# PCB.net
KiCad netlist of a schematic drawn in EasyEDA Pro
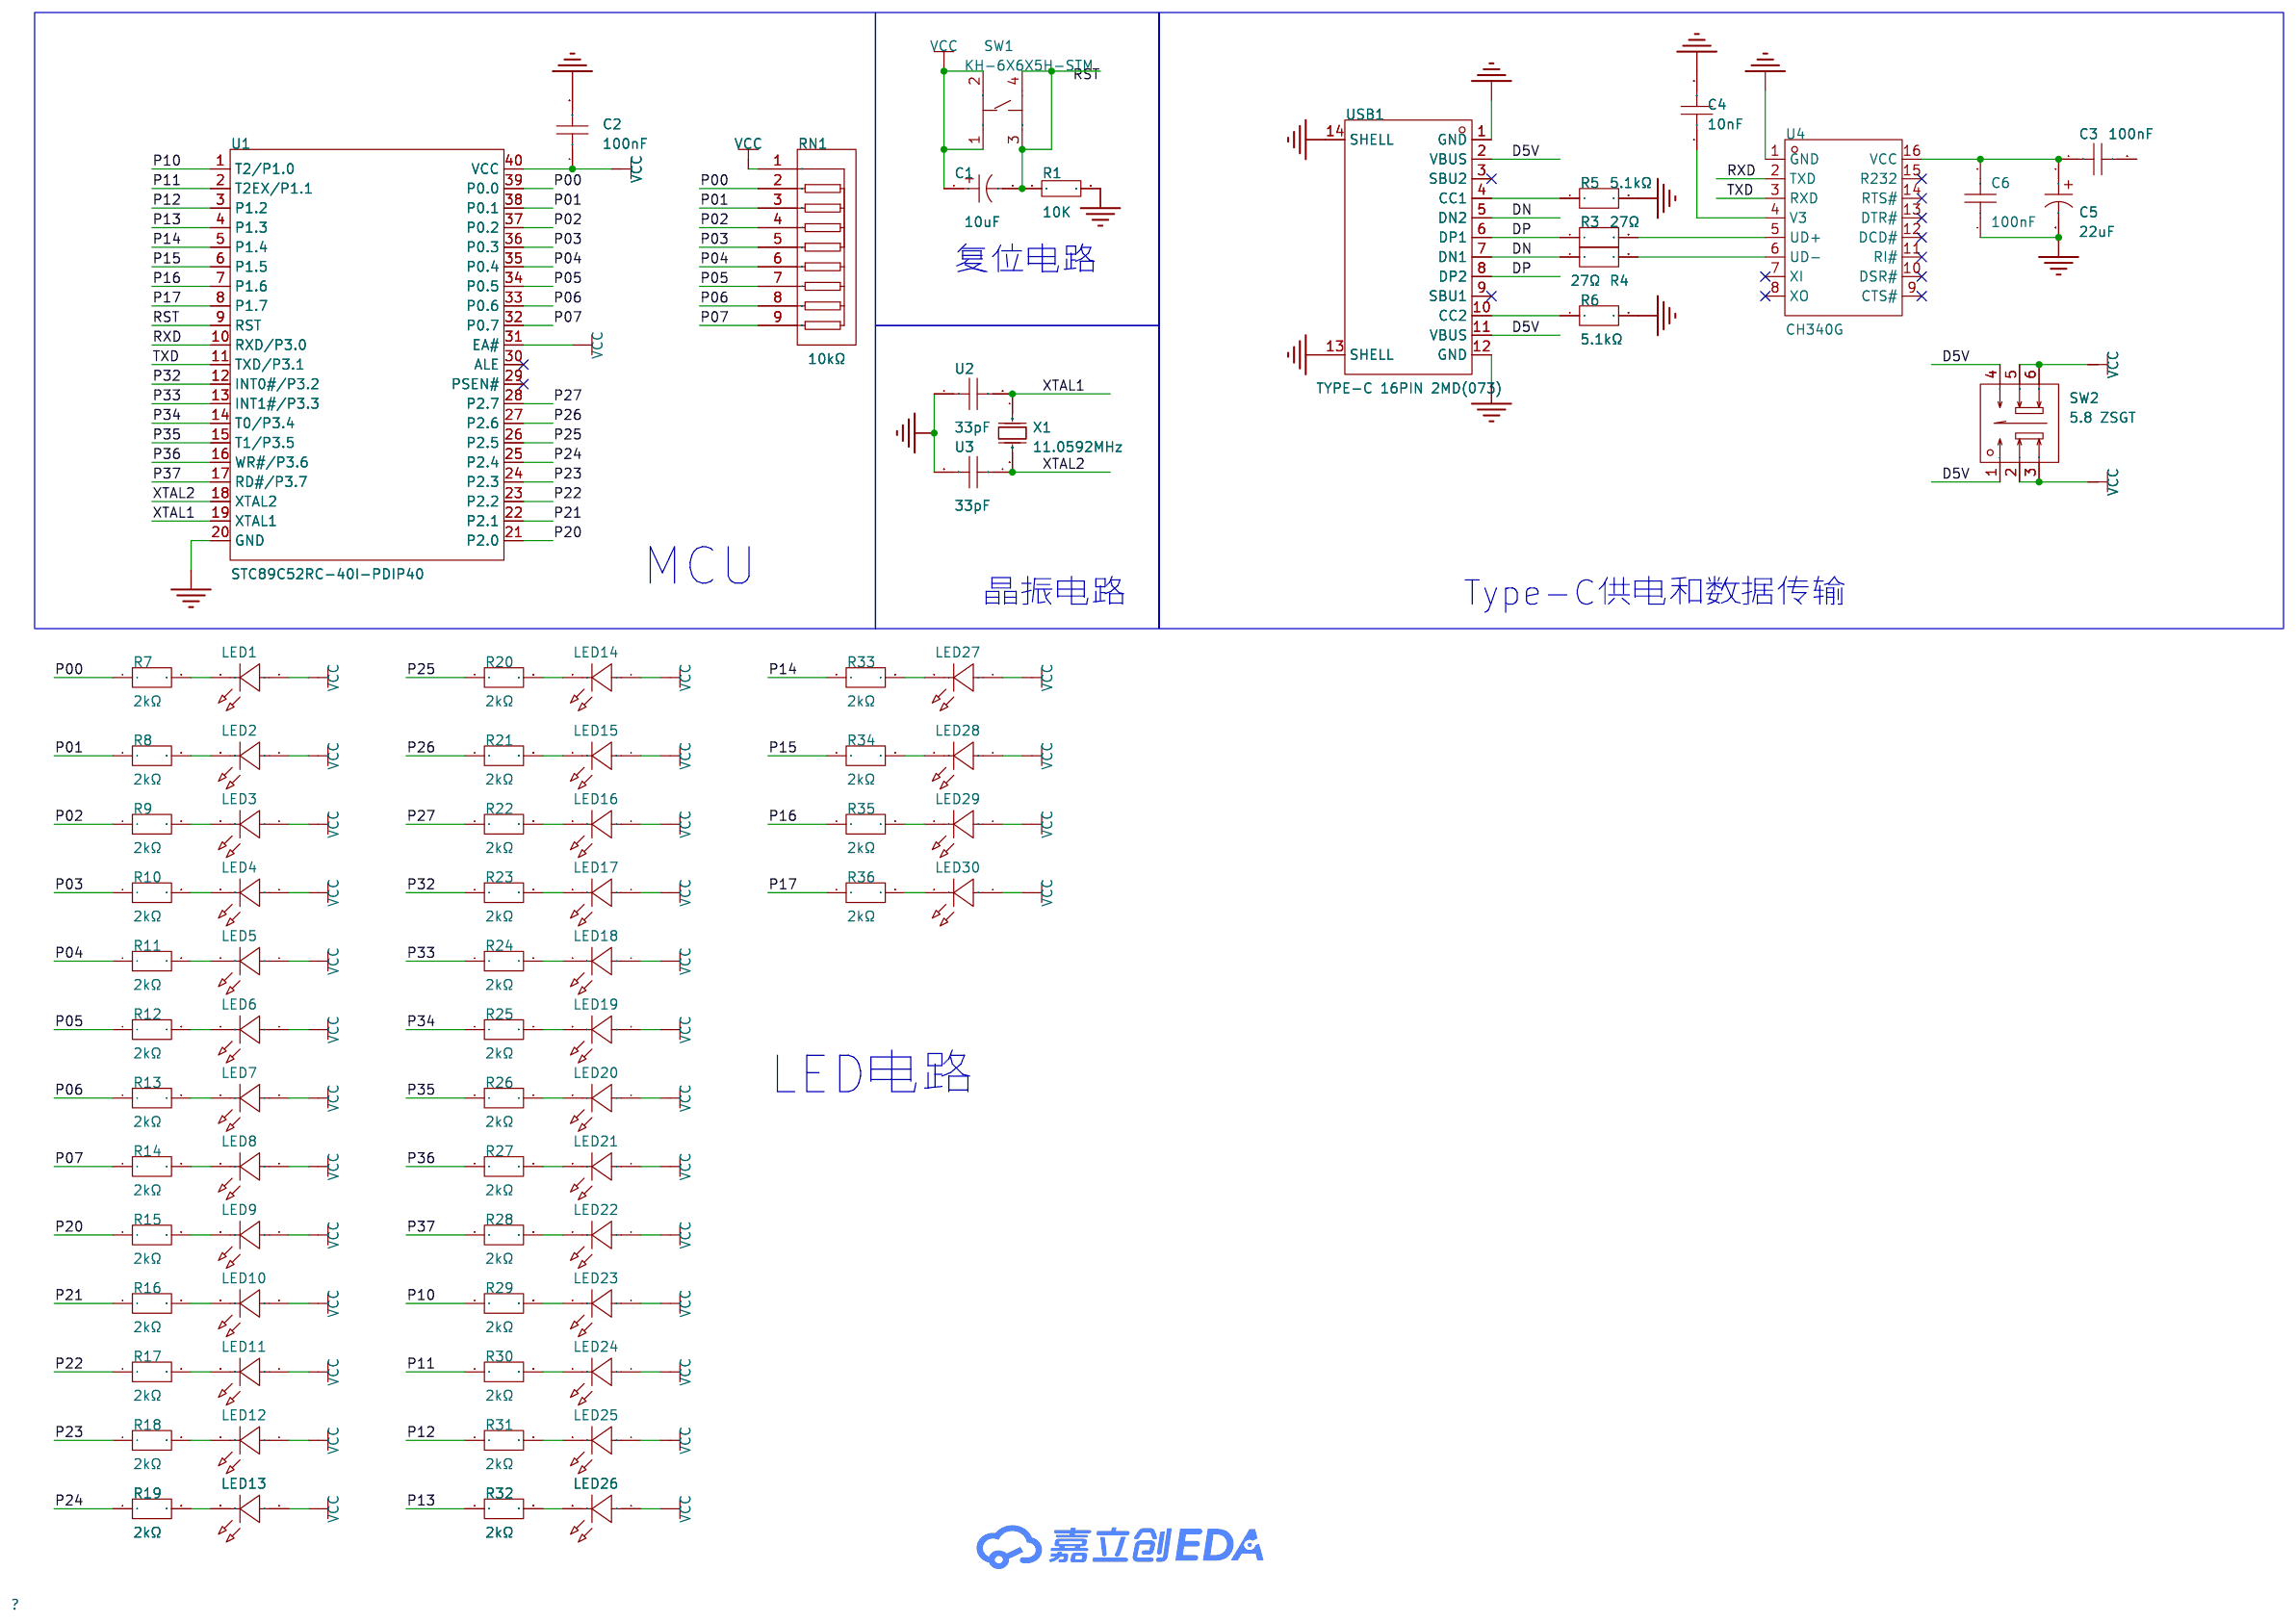
[diagram p0: schematic sheet]

(export (version "E")
  (design (tool "Eeschema 10.0.6"))
  (components
    (comp (ref "C1")
      (value "10uF")
      (footprint "easyedapro:CAP-TH_BD10.0-P5.00-D0.6-FD_1")
      (description "容值:10uF;精度:±20%;额定电压:450V;纹波电流:200mA@100kHz;等效串联电阻(ESR):9Ω@100kHz;")
      (fields (field (name "Manufacturer Part") "CV100MPA16B") (field (name "Manufacturer") "TWBOR(伯鸿)"))
      (libsource (lib "easyedapro") (part "CV100MPA16B"))
    )
    (comp (ref "C2")
      (value "100nF")
      (footprint "easyedapro:C0603")
      (description "容值:100nF;精度:±10%;额定电压:25V;温度系数:X7R;")
      (fields
        (field (name "Manufacturer Part") "0603X7R104K250NT")
        (field (name "Manufacturer") "AIDE(爱迪电容)")
      )
      (libsource (lib "easyedapro") (part "0603X7R104K250NT"))
    )
    (comp (ref "C3")
      (value "100nF")
      (footprint "easyedapro:C0603")
      (description "容值:100nF;精度:±10%;额定电压:25V;温度系数:X7R;")
      (fields
        (field (name "Manufacturer Part") "0603X7R104K250NT")
        (field (name "Manufacturer") "AIDE(爱迪电容)")
      )
      (libsource (lib "easyedapro") (part "0603X7R104K250NT"))
    )
    (comp (ref "C4")
      (value "10nF")
      (footprint "easyedapro:C0603")
      (description "容值:10nF;精度:±10%;额定电压:200V;温度系数:X7R;")
      (fields
        (field (name "Manufacturer Part") "C0603X103K2RECAUTO")
        (field (name "Manufacturer") "KEMET(基美)")
      )
      (libsource (lib "easyedapro") (part "C0603X103K2RECAUTO"))
    )
    (comp (ref "C5")
      (value "22uF")
      (footprint "easyedapro:CAP-SMD_BD5.0-L5.3-W5.3-LS6.0-FD-H5.7")
      (description "容值:22uF;精度:±20%;额定电压:35V;纹波电流:95mA@120Hz;等效串联电阻(ESR):1.8Ω;")
      (fields (field (name "Manufacturer Part") "JVE35V22M5X6") (field (name "Manufacturer") "捷而瑞"))
      (libsource (lib "easyedapro") (part "JVE35V22M5X6"))
    )
    (comp (ref "C6")
      (value "100nF")
      (footprint "easyedapro:C0603")
      (description "容值:100nF;精度:±10%;额定电压:25V;温度系数:X7R;")
      (fields
        (field (name "Manufacturer Part") "0603X7R104K250NT")
        (field (name "Manufacturer") "AIDE(爱迪电容)")
      )
      (libsource (lib "easyedapro") (part "0603X7R104K250NT"))
    )
    (comp (ref "LED1")
      (value "L-7113SGC")
      (footprint "easyedapro:LED-TH_BD5.9-P2.54-FD")
      (fields (field (name "Manufacturer") "Kingbright"))
      (libsource (lib "easyedapro") (part "L-7113SGC"))
    )
    (comp (ref "LED2")
      (value "L-7113SGC")
      (footprint "easyedapro:LED-TH_BD5.9-P2.54-FD")
      (fields (field (name "Manufacturer") "Kingbright"))
      (libsource (lib "easyedapro") (part "L-7113SGC"))
    )
    (comp (ref "LED3")
      (value "L-7113SGC")
      (footprint "easyedapro:LED-TH_BD5.9-P2.54-FD")
      (fields (field (name "Manufacturer") "Kingbright"))
      (libsource (lib "easyedapro") (part "L-7113SGC"))
    )
    (comp (ref "LED4")
      (value "L-7113SGC")
      (footprint "easyedapro:LED-TH_BD5.9-P2.54-FD")
      (fields (field (name "Manufacturer") "Kingbright"))
      (libsource (lib "easyedapro") (part "L-7113SGC"))
    )
    (comp (ref "LED5")
      (value "L-7113SGC")
      (footprint "easyedapro:LED-TH_BD5.9-P2.54-FD")
      (fields (field (name "Manufacturer") "Kingbright"))
      (libsource (lib "easyedapro") (part "L-7113SGC"))
    )
    (comp (ref "LED6")
      (value "L-7113SGC")
      (footprint "easyedapro:LED-TH_BD5.9-P2.54-FD")
      (fields (field (name "Manufacturer") "Kingbright"))
      (libsource (lib "easyedapro") (part "L-7113SGC"))
    )
    (comp (ref "LED7")
      (value "L-7113SGC")
      (footprint "easyedapro:LED-TH_BD5.9-P2.54-FD")
      (fields (field (name "Manufacturer") "Kingbright"))
      (libsource (lib "easyedapro") (part "L-7113SGC"))
    )
    (comp (ref "LED8")
      (value "L-7113SGC")
      (footprint "easyedapro:LED-TH_BD5.9-P2.54-FD")
      (fields (field (name "Manufacturer") "Kingbright"))
      (libsource (lib "easyedapro") (part "L-7113SGC"))
    )
    (comp (ref "LED9")
      (value "L-7113SGC")
      (footprint "easyedapro:LED-TH_BD5.9-P2.54-FD")
      (fields (field (name "Manufacturer") "Kingbright"))
      (libsource (lib "easyedapro") (part "L-7113SGC"))
    )
    (comp (ref "LED10")
      (value "L-7113SGC")
      (footprint "easyedapro:LED-TH_BD5.9-P2.54-FD")
      (fields (field (name "Manufacturer") "Kingbright"))
      (libsource (lib "easyedapro") (part "L-7113SGC"))
    )
    (comp (ref "LED11")
      (value "L-7113SGC")
      (footprint "easyedapro:LED-TH_BD5.9-P2.54-FD")
      (fields (field (name "Manufacturer") "Kingbright"))
      (libsource (lib "easyedapro") (part "L-7113SGC"))
    )
    (comp (ref "LED12")
      (value "L-7113SGC")
      (footprint "easyedapro:LED-TH_BD5.9-P2.54-FD")
      (fields (field (name "Manufacturer") "Kingbright"))
      (libsource (lib "easyedapro") (part "L-7113SGC"))
    )
    (comp (ref "LED13")
      (value "L-7113SGC")
      (footprint "easyedapro:LED-TH_BD5.9-P2.54-FD")
      (fields (field (name "Manufacturer") "Kingbright"))
      (libsource (lib "easyedapro") (part "L-7113SGC"))
    )
    (comp (ref "LED14")
      (value "L-7113SGC")
      (footprint "easyedapro:LED-TH_BD5.9-P2.54-FD")
      (fields (field (name "Manufacturer") "Kingbright"))
      (libsource (lib "easyedapro") (part "L-7113SGC"))
    )
    (comp (ref "LED15")
      (value "L-7113SGC")
      (footprint "easyedapro:LED-TH_BD5.9-P2.54-FD")
      (fields (field (name "Manufacturer") "Kingbright"))
      (libsource (lib "easyedapro") (part "L-7113SGC"))
    )
    (comp (ref "LED16")
      (value "L-7113SGC")
      (footprint "easyedapro:LED-TH_BD5.9-P2.54-FD")
      (fields (field (name "Manufacturer") "Kingbright"))
      (libsource (lib "easyedapro") (part "L-7113SGC"))
    )
    (comp (ref "LED17")
      (value "L-7113SGC")
      (footprint "easyedapro:LED-TH_BD5.9-P2.54-FD")
      (fields (field (name "Manufacturer") "Kingbright"))
      (libsource (lib "easyedapro") (part "L-7113SGC"))
    )
    (comp (ref "LED18")
      (value "L-7113SGC")
      (footprint "easyedapro:LED-TH_BD5.9-P2.54-FD")
      (fields (field (name "Manufacturer") "Kingbright"))
      (libsource (lib "easyedapro") (part "L-7113SGC"))
    )
    (comp (ref "LED19")
      (value "L-7113SGC")
      (footprint "easyedapro:LED-TH_BD5.9-P2.54-FD")
      (fields (field (name "Manufacturer") "Kingbright"))
      (libsource (lib "easyedapro") (part "L-7113SGC"))
    )
    (comp (ref "LED20")
      (value "L-7113SGC")
      (footprint "easyedapro:LED-TH_BD5.9-P2.54-FD")
      (fields (field (name "Manufacturer") "Kingbright"))
      (libsource (lib "easyedapro") (part "L-7113SGC"))
    )
    (comp (ref "LED21")
      (value "L-7113SGC")
      (footprint "easyedapro:LED-TH_BD5.9-P2.54-FD")
      (fields (field (name "Manufacturer") "Kingbright"))
      (libsource (lib "easyedapro") (part "L-7113SGC"))
    )
    (comp (ref "LED22")
      (value "L-7113SGC")
      (footprint "easyedapro:LED-TH_BD5.9-P2.54-FD")
      (fields (field (name "Manufacturer") "Kingbright"))
      (libsource (lib "easyedapro") (part "L-7113SGC"))
    )
    (comp (ref "LED23")
      (value "L-7113SGC")
      (footprint "easyedapro:LED-TH_BD5.9-P2.54-FD")
      (fields (field (name "Manufacturer") "Kingbright"))
      (libsource (lib "easyedapro") (part "L-7113SGC"))
    )
    (comp (ref "LED24")
      (value "L-7113SGC")
      (footprint "easyedapro:LED-TH_BD5.9-P2.54-FD")
      (fields (field (name "Manufacturer") "Kingbright"))
      (libsource (lib "easyedapro") (part "L-7113SGC"))
    )
    (comp (ref "LED25")
      (value "L-7113SGC")
      (footprint "easyedapro:LED-TH_BD5.9-P2.54-FD")
      (fields (field (name "Manufacturer") "Kingbright"))
      (libsource (lib "easyedapro") (part "L-7113SGC"))
    )
    (comp (ref "LED26")
      (value "L-7113SGC")
      (footprint "easyedapro:LED-TH_BD5.9-P2.54-FD")
      (fields (field (name "Manufacturer") "Kingbright"))
      (libsource (lib "easyedapro") (part "L-7113SGC"))
    )
    (comp (ref "LED27")
      (value "L-7113SGC")
      (footprint "easyedapro:LED-TH_BD5.9-P2.54-FD")
      (fields (field (name "Manufacturer") "Kingbright"))
      (libsource (lib "easyedapro") (part "L-7113SGC"))
    )
    (comp (ref "LED28")
      (value "L-7113SGC")
      (footprint "easyedapro:LED-TH_BD5.9-P2.54-FD")
      (fields (field (name "Manufacturer") "Kingbright"))
      (libsource (lib "easyedapro") (part "L-7113SGC"))
    )
    (comp (ref "LED29")
      (value "L-7113SGC")
      (footprint "easyedapro:LED-TH_BD5.9-P2.54-FD")
      (fields (field (name "Manufacturer") "Kingbright"))
      (libsource (lib "easyedapro") (part "L-7113SGC"))
    )
    (comp (ref "LED30")
      (value "L-7113SGC")
      (footprint "easyedapro:LED-TH_BD5.9-P2.54-FD")
      (fields (field (name "Manufacturer") "Kingbright"))
      (libsource (lib "easyedapro") (part "L-7113SGC"))
    )
    (comp (ref "R1") (value "10K") (footprint "easyedapro:R0603") (libsource (lib "easyedapro") (part "电阻")))
    (comp (ref "R3")
      (value "27Ω")
      (footprint "easyedapro:R0805")
      (description "电阻类型:厚膜电阻;阻值:27Ω;精度:±5%;功率:125mW;工作电压:150V;温度系数:±100ppm/°C;")
      (fields (field (name "Manufacturer Part") "FRC0805J270 TS") (field (name "Manufacturer") "FOJAN(富捷)"))
      (libsource (lib "easyedapro") (part "FRC0805J270 TS"))
    )
    (comp (ref "R4")
      (value "27Ω")
      (footprint "easyedapro:R0805")
      (description "电阻类型:厚膜电阻;阻值:27Ω;精度:±5%;功率:125mW;工作电压:150V;温度系数:±100ppm/°C;")
      (fields (field (name "Manufacturer Part") "FRC0805J270 TS") (field (name "Manufacturer") "FOJAN(富捷)"))
      (libsource (lib "easyedapro") (part "FRC0805J270 TS"))
    )
    (comp (ref "R5")
      (value "5.1kΩ")
      (footprint "easyedapro:R0603")
      (description "电阻类型:薄膜电阻;阻值:5.1kΩ;精度:±0.01%;功率:100mW;温度系数:±2ppm/°C;")
      (fields
        (field (name "Manufacturer Part") "RNCF0603TKW5K10")
        (field (name "Manufacturer") "SEI(Stackpole Electronics Inc.)")
      )
      (libsource (lib "easyedapro") (part "RNCF0603TKW5K10"))
    )
    (comp (ref "R6")
      (value "5.1kΩ")
      (footprint "easyedapro:R0603")
      (description "电阻类型:薄膜电阻;阻值:5.1kΩ;精度:±0.01%;功率:100mW;温度系数:±2ppm/°C;")
      (fields
        (field (name "Manufacturer Part") "RNCF0603TKW5K10")
        (field (name "Manufacturer") "SEI(Stackpole Electronics Inc.)")
      )
      (libsource (lib "easyedapro") (part "RNCF0603TKW5K10"))
    )
    (comp (ref "R7")
      (value "2kΩ")
      (footprint "easyedapro:R0402")
      (description "电阻类型:厚膜电阻;阻值:2kΩ;精度:±1%;功率:200mW;工作电压:50V;温度系数:±100ppm/°C;")
      (fields (field (name "Manufacturer Part") "RCS04022K00FKED") (field (name "Manufacturer") "VISHAY(威世)"))
      (libsource (lib "easyedapro") (part "RCS04022K00FKED"))
    )
    (comp (ref "R8")
      (value "2kΩ")
      (footprint "easyedapro:R0402")
      (description "电阻类型:厚膜电阻;阻值:2kΩ;精度:±1%;功率:200mW;工作电压:50V;温度系数:±100ppm/°C;")
      (fields (field (name "Manufacturer Part") "RCS04022K00FKED") (field (name "Manufacturer") "VISHAY(威世)"))
      (libsource (lib "easyedapro") (part "RCS04022K00FKED"))
    )
    (comp (ref "R9")
      (value "2kΩ")
      (footprint "easyedapro:R0402")
      (description "电阻类型:厚膜电阻;阻值:2kΩ;精度:±1%;功率:200mW;工作电压:50V;温度系数:±100ppm/°C;")
      (fields (field (name "Manufacturer Part") "RCS04022K00FKED") (field (name "Manufacturer") "VISHAY(威世)"))
      (libsource (lib "easyedapro") (part "RCS04022K00FKED"))
    )
    (comp (ref "R10")
      (value "2kΩ")
      (footprint "easyedapro:R0402")
      (description "电阻类型:厚膜电阻;阻值:2kΩ;精度:±1%;功率:200mW;工作电压:50V;温度系数:±100ppm/°C;")
      (fields (field (name "Manufacturer Part") "RCS04022K00FKED") (field (name "Manufacturer") "VISHAY(威世)"))
      (libsource (lib "easyedapro") (part "RCS04022K00FKED"))
    )
    (comp (ref "R11")
      (value "2kΩ")
      (footprint "easyedapro:R0402")
      (description "电阻类型:厚膜电阻;阻值:2kΩ;精度:±1%;功率:200mW;工作电压:50V;温度系数:±100ppm/°C;")
      (fields (field (name "Manufacturer Part") "RCS04022K00FKED") (field (name "Manufacturer") "VISHAY(威世)"))
      (libsource (lib "easyedapro") (part "RCS04022K00FKED"))
    )
    (comp (ref "R12")
      (value "2kΩ")
      (footprint "easyedapro:R0402")
      (description "电阻类型:厚膜电阻;阻值:2kΩ;精度:±1%;功率:200mW;工作电压:50V;温度系数:±100ppm/°C;")
      (fields (field (name "Manufacturer Part") "RCS04022K00FKED") (field (name "Manufacturer") "VISHAY(威世)"))
      (libsource (lib "easyedapro") (part "RCS04022K00FKED"))
    )
    (comp (ref "R13")
      (value "2kΩ")
      (footprint "easyedapro:R0402")
      (description "电阻类型:厚膜电阻;阻值:2kΩ;精度:±1%;功率:200mW;工作电压:50V;温度系数:±100ppm/°C;")
      (fields (field (name "Manufacturer Part") "RCS04022K00FKED") (field (name "Manufacturer") "VISHAY(威世)"))
      (libsource (lib "easyedapro") (part "RCS04022K00FKED"))
    )
    (comp (ref "R14")
      (value "2kΩ")
      (footprint "easyedapro:R0402")
      (description "电阻类型:厚膜电阻;阻值:2kΩ;精度:±1%;功率:200mW;工作电压:50V;温度系数:±100ppm/°C;")
      (fields (field (name "Manufacturer Part") "RCS04022K00FKED") (field (name "Manufacturer") "VISHAY(威世)"))
      (libsource (lib "easyedapro") (part "RCS04022K00FKED"))
    )
    (comp (ref "R15")
      (value "2kΩ")
      (footprint "easyedapro:R0402")
      (description "电阻类型:厚膜电阻;阻值:2kΩ;精度:±1%;功率:200mW;工作电压:50V;温度系数:±100ppm/°C;")
      (fields (field (name "Manufacturer Part") "RCS04022K00FKED") (field (name "Manufacturer") "VISHAY(威世)"))
      (libsource (lib "easyedapro") (part "RCS04022K00FKED"))
    )
    (comp (ref "R16")
      (value "2kΩ")
      (footprint "easyedapro:R0402")
      (description "电阻类型:厚膜电阻;阻值:2kΩ;精度:±1%;功率:200mW;工作电压:50V;温度系数:±100ppm/°C;")
      (fields (field (name "Manufacturer Part") "RCS04022K00FKED") (field (name "Manufacturer") "VISHAY(威世)"))
      (libsource (lib "easyedapro") (part "RCS04022K00FKED"))
    )
    (comp (ref "R17")
      (value "2kΩ")
      (footprint "easyedapro:R0402")
      (description "电阻类型:厚膜电阻;阻值:2kΩ;精度:±1%;功率:200mW;工作电压:50V;温度系数:±100ppm/°C;")
      (fields (field (name "Manufacturer Part") "RCS04022K00FKED") (field (name "Manufacturer") "VISHAY(威世)"))
      (libsource (lib "easyedapro") (part "RCS04022K00FKED"))
    )
    (comp (ref "R18")
      (value "2kΩ")
      (footprint "easyedapro:R0402")
      (description "电阻类型:厚膜电阻;阻值:2kΩ;精度:±1%;功率:200mW;工作电压:50V;温度系数:±100ppm/°C;")
      (fields (field (name "Manufacturer Part") "RCS04022K00FKED") (field (name "Manufacturer") "VISHAY(威世)"))
      (libsource (lib "easyedapro") (part "RCS04022K00FKED"))
    )
    (comp (ref "R19")
      (value "2kΩ")
      (footprint "easyedapro:R0402")
      (description "电阻类型:厚膜电阻;阻值:2kΩ;精度:±1%;功率:200mW;工作电压:50V;温度系数:±100ppm/°C;")
      (fields (field (name "Manufacturer Part") "RCS04022K00FKED") (field (name "Manufacturer") "VISHAY(威世)"))
      (libsource (lib "easyedapro") (part "RCS04022K00FKED"))
    )
    (comp (ref "R20")
      (value "2kΩ")
      (footprint "easyedapro:R0402")
      (description "电阻类型:厚膜电阻;阻值:2kΩ;精度:±1%;功率:200mW;工作电压:50V;温度系数:±100ppm/°C;")
      (fields (field (name "Manufacturer Part") "RCS04022K00FKED") (field (name "Manufacturer") "VISHAY(威世)"))
      (libsource (lib "easyedapro") (part "RCS04022K00FKED"))
    )
    (comp (ref "R21")
      (value "2kΩ")
      (footprint "easyedapro:R0402")
      (description "电阻类型:厚膜电阻;阻值:2kΩ;精度:±1%;功率:200mW;工作电压:50V;温度系数:±100ppm/°C;")
      (fields (field (name "Manufacturer Part") "RCS04022K00FKED") (field (name "Manufacturer") "VISHAY(威世)"))
      (libsource (lib "easyedapro") (part "RCS04022K00FKED"))
    )
    (comp (ref "R22")
      (value "2kΩ")
      (footprint "easyedapro:R0402")
      (description "电阻类型:厚膜电阻;阻值:2kΩ;精度:±1%;功率:200mW;工作电压:50V;温度系数:±100ppm/°C;")
      (fields (field (name "Manufacturer Part") "RCS04022K00FKED") (field (name "Manufacturer") "VISHAY(威世)"))
      (libsource (lib "easyedapro") (part "RCS04022K00FKED"))
    )
    (comp (ref "R23")
      (value "2kΩ")
      (footprint "easyedapro:R0402")
      (description "电阻类型:厚膜电阻;阻值:2kΩ;精度:±1%;功率:200mW;工作电压:50V;温度系数:±100ppm/°C;")
      (fields (field (name "Manufacturer Part") "RCS04022K00FKED") (field (name "Manufacturer") "VISHAY(威世)"))
      (libsource (lib "easyedapro") (part "RCS04022K00FKED"))
    )
    (comp (ref "R24")
      (value "2kΩ")
      (footprint "easyedapro:R0402")
      (description "电阻类型:厚膜电阻;阻值:2kΩ;精度:±1%;功率:200mW;工作电压:50V;温度系数:±100ppm/°C;")
      (fields (field (name "Manufacturer Part") "RCS04022K00FKED") (field (name "Manufacturer") "VISHAY(威世)"))
      (libsource (lib "easyedapro") (part "RCS04022K00FKED"))
    )
    (comp (ref "R25")
      (value "2kΩ")
      (footprint "easyedapro:R0402")
      (description "电阻类型:厚膜电阻;阻值:2kΩ;精度:±1%;功率:200mW;工作电压:50V;温度系数:±100ppm/°C;")
      (fields (field (name "Manufacturer Part") "RCS04022K00FKED") (field (name "Manufacturer") "VISHAY(威世)"))
      (libsource (lib "easyedapro") (part "RCS04022K00FKED"))
    )
    (comp (ref "R26")
      (value "2kΩ")
      (footprint "easyedapro:R0402")
      (description "电阻类型:厚膜电阻;阻值:2kΩ;精度:±1%;功率:200mW;工作电压:50V;温度系数:±100ppm/°C;")
      (fields (field (name "Manufacturer Part") "RCS04022K00FKED") (field (name "Manufacturer") "VISHAY(威世)"))
      (libsource (lib "easyedapro") (part "RCS04022K00FKED"))
    )
    (comp (ref "R27")
      (value "2kΩ")
      (footprint "easyedapro:R0402")
      (description "电阻类型:厚膜电阻;阻值:2kΩ;精度:±1%;功率:200mW;工作电压:50V;温度系数:±100ppm/°C;")
      (fields (field (name "Manufacturer Part") "RCS04022K00FKED") (field (name "Manufacturer") "VISHAY(威世)"))
      (libsource (lib "easyedapro") (part "RCS04022K00FKED"))
    )
    (comp (ref "R28")
      (value "2kΩ")
      (footprint "easyedapro:R0402")
      (description "电阻类型:厚膜电阻;阻值:2kΩ;精度:±1%;功率:200mW;工作电压:50V;温度系数:±100ppm/°C;")
      (fields (field (name "Manufacturer Part") "RCS04022K00FKED") (field (name "Manufacturer") "VISHAY(威世)"))
      (libsource (lib "easyedapro") (part "RCS04022K00FKED"))
    )
    (comp (ref "R29")
      (value "2kΩ")
      (footprint "easyedapro:R0402")
      (description "电阻类型:厚膜电阻;阻值:2kΩ;精度:±1%;功率:200mW;工作电压:50V;温度系数:±100ppm/°C;")
      (fields (field (name "Manufacturer Part") "RCS04022K00FKED") (field (name "Manufacturer") "VISHAY(威世)"))
      (libsource (lib "easyedapro") (part "RCS04022K00FKED"))
    )
    (comp (ref "R30")
      (value "2kΩ")
      (footprint "easyedapro:R0402")
      (description "电阻类型:厚膜电阻;阻值:2kΩ;精度:±1%;功率:200mW;工作电压:50V;温度系数:±100ppm/°C;")
      (fields (field (name "Manufacturer Part") "RCS04022K00FKED") (field (name "Manufacturer") "VISHAY(威世)"))
      (libsource (lib "easyedapro") (part "RCS04022K00FKED"))
    )
    (comp (ref "R31")
      (value "2kΩ")
      (footprint "easyedapro:R0402")
      (description "电阻类型:厚膜电阻;阻值:2kΩ;精度:±1%;功率:200mW;工作电压:50V;温度系数:±100ppm/°C;")
      (fields (field (name "Manufacturer Part") "RCS04022K00FKED") (field (name "Manufacturer") "VISHAY(威世)"))
      (libsource (lib "easyedapro") (part "RCS04022K00FKED"))
    )
    (comp (ref "R32")
      (value "2kΩ")
      (footprint "easyedapro:R0402")
      (description "电阻类型:厚膜电阻;阻值:2kΩ;精度:±1%;功率:200mW;工作电压:50V;温度系数:±100ppm/°C;")
      (fields (field (name "Manufacturer Part") "RCS04022K00FKED") (field (name "Manufacturer") "VISHAY(威世)"))
      (libsource (lib "easyedapro") (part "RCS04022K00FKED"))
    )
    (comp (ref "R33")
      (value "2kΩ")
      (footprint "easyedapro:R0402")
      (description "电阻类型:厚膜电阻;阻值:2kΩ;精度:±1%;功率:200mW;工作电压:50V;温度系数:±100ppm/°C;")
      (fields (field (name "Manufacturer Part") "RCS04022K00FKED") (field (name "Manufacturer") "VISHAY(威世)"))
      (libsource (lib "easyedapro") (part "RCS04022K00FKED"))
    )
    (comp (ref "R34")
      (value "2kΩ")
      (footprint "easyedapro:R0402")
      (description "电阻类型:厚膜电阻;阻值:2kΩ;精度:±1%;功率:200mW;工作电压:50V;温度系数:±100ppm/°C;")
      (fields (field (name "Manufacturer Part") "RCS04022K00FKED") (field (name "Manufacturer") "VISHAY(威世)"))
      (libsource (lib "easyedapro") (part "RCS04022K00FKED"))
    )
    (comp (ref "R35")
      (value "2kΩ")
      (footprint "easyedapro:R0402")
      (description "电阻类型:厚膜电阻;阻值:2kΩ;精度:±1%;功率:200mW;工作电压:50V;温度系数:±100ppm/°C;")
      (fields (field (name "Manufacturer Part") "RCS04022K00FKED") (field (name "Manufacturer") "VISHAY(威世)"))
      (libsource (lib "easyedapro") (part "RCS04022K00FKED"))
    )
    (comp (ref "R36")
      (value "2kΩ")
      (footprint "easyedapro:R0402")
      (description "电阻类型:厚膜电阻;阻值:2kΩ;精度:±1%;功率:200mW;工作电压:50V;温度系数:±100ppm/°C;")
      (fields (field (name "Manufacturer Part") "RCS04022K00FKED") (field (name "Manufacturer") "VISHAY(威世)"))
      (libsource (lib "easyedapro") (part "RCS04022K00FKED"))
    )
    (comp (ref "RN1")
      (value "10kΩ")
      (footprint "easyedapro:RES-ARRAY-TH_9P-P2.54-D1.0")
      (description "电阻器数:-;阻值:-;单个元件功率:-;")
      (fields (field (name "Manufacturer Part") "排阻 10 K 5%"))
      (libsource (lib "easyedapro") (part "10 K 5%"))
    )
    (comp (ref "SW1")
      (value "KH-6X6X5H-STM")
      (footprint "easyedapro:SW-SMD_4P-L6.0-W6.0-P4.50-LS9.0_H5.0")
      (description "电路结构:单刀单掷;按钮形状:圆形按钮;安装方式:立贴;开关长度:6mm;开关宽度:6mm;开关高度:5mm;带支架:不带;触点电流:50mA;额定电压(DC):12V;机械寿命:8万次;")
      (fields (field (name "Manufacturer") "kinghelm(金航标)"))
      (libsource (lib "easyedapro") (part "KH-6X6X5H-STM"))
    )
    (comp (ref "SW2")
      (value "5.8 ZSGT")
      (footprint "easyedapro:SW-TH_5.8ZSGT")
      (description "电路结构:双刀双掷;自锁/无锁:自锁;安装方式:直插;触点电流:110mA;额定电压 (DC):30V;带灯:不带;作用力:1.5N;机械寿命:10万次;")
      (fields (field (name "Manufacturer") "SHOU HAN(首韩)"))
      (libsource (lib "easyedapro") (part "5.8 ZSGT"))
    )
    (comp (ref "U1")
      (value "STC89C52RC-40I-PDIP40")
      (footprint "easyedapro:DIP-40_L52.0-W13.7-P2.54-LS15.2-BL")
      (description "CPU内核:51系列;应用领域:-;")
      (fields (field (name "Manufacturer") "STC"))
      (libsource (lib "easyedapro") (part "STC89C52RC-40I"))
    )
    (comp (ref "U2")
      (value "33pF")
      (footprint "easyedapro:C0603")
      (description "容值:33pF;精度:±1%;额定电压:50V;温度系数:-;")
      (fields
        (field (name "Manufacturer Part") "GRM1885C1H330FA01D")
        (field (name "Manufacturer") "muRata(村田)")
      )
      (libsource (lib "easyedapro") (part "GRM1885C1H330FA01D"))
    )
    (comp (ref "U3")
      (value "33pF")
      (footprint "easyedapro:C0603")
      (description "容值:33pF;精度:±1%;额定电压:50V;温度系数:-;")
      (fields
        (field (name "Manufacturer Part") "GRM1885C1H330FA01D")
        (field (name "Manufacturer") "muRata(村田)")
      )
      (libsource (lib "easyedapro") (part "GRM1885C1H330FA01D"))
    )
    (comp (ref "U4")
      (value "CH340G")
      (footprint "easyedapro:SOIC-16_L9.9-W3.9-P1.27-LS6.0-BL")
      (description "应用功能:USB转UART;接口协议:USB 2.0;数据速率:2Mbps;")
      (fields (field (name "Manufacturer") "WCH(南京沁恒)"))
      (libsource (lib "easyedapro") (part "CH340G"))
    )
    (comp (ref "USB1")
      (value "TYPE-C 16PIN 2MD(073)")
      (footprint "easyedapro:USB-C-SMD_TYPE-C-6PIN-2MD-073")
      (description "连接器类型:Type-C;协议标准:USB 3.1;公母:母;安装方式:卧贴;触点数量:16P;端口数量:1;额定电流 - 电源:3A;工作温度:-25°C~+85°C;")
      (fields (field (name "Manufacturer") "SHOU HAN(首韩)"))
      (libsource (lib "easyedapro") (part "TYPE-C 16PIN 2MD(073)"))
    )
    (comp (ref "X1")
      (value "11.0592MHz")
      (footprint "easyedapro:HC-49US_L11.5-W4.5-P4.88")
      (description "晶振类型:直插晶振;频率:11.0592MHz;常温频差:±20ppm;负载电容:20pF;频率稳定度:±30ppm;")
      (fields
        (field (name "Manufacturer Part") "X49SD110592MSD2SC")
        (field (name "Manufacturer") "YXC(扬兴晶振)")
      )
      (libsource (lib "easyedapro") (part "X49SD110592MSD2SC"))
    )
  )
  (nets
    (net (code "1") (name "/D5V") (class "Default")
      (node (ref "SW2") (pin "1") (pinfunction "1_1") (pintype "unspecified"))
      (node (ref "SW2") (pin "4") (pinfunction "4_4") (pintype "unspecified"))
      (node (ref "USB1") (pin "11") (pinfunction "VBUS_11") (pintype "unspecified"))
      (node (ref "USB1") (pin "2") (pinfunction "VBUS_2") (pintype "unspecified"))
    )
    (net (code "2") (name "/DN") (class "Default")
      (node (ref "R4") (pin "1") (pinfunction "1_1") (pintype "unspecified"))
      (node (ref "USB1") (pin "5") (pinfunction "DN2_5") (pintype "unspecified"))
      (node (ref "USB1") (pin "7") (pinfunction "DN1_7") (pintype "unspecified"))
    )
    (net (code "3") (name "/DP") (class "Default")
      (node (ref "R3") (pin "1") (pinfunction "1_1") (pintype "unspecified"))
      (node (ref "USB1") (pin "6") (pinfunction "DP1_6") (pintype "unspecified"))
      (node (ref "USB1") (pin "8") (pinfunction "DP2_8") (pintype "unspecified"))
    )
    (net (code "4") (name "/P00") (class "Default")
      (node (ref "R7") (pin "1") (pinfunction "1_1") (pintype "unspecified"))
      (node (ref "RN1") (pin "2") (pinfunction "2_2") (pintype "input"))
      (node (ref "U1") (pin "39") (pinfunction "P0.0_39") (pintype "unspecified"))
    )
    (net (code "5") (name "/P01") (class "Default")
      (node (ref "R8") (pin "1") (pinfunction "1_1") (pintype "unspecified"))
      (node (ref "RN1") (pin "3") (pinfunction "3_3") (pintype "input"))
      (node (ref "U1") (pin "38") (pinfunction "P0.1_38") (pintype "unspecified"))
    )
    (net (code "6") (name "/P02") (class "Default")
      (node (ref "R9") (pin "1") (pinfunction "1_1") (pintype "unspecified"))
      (node (ref "RN1") (pin "4") (pinfunction "4_4") (pintype "input"))
      (node (ref "U1") (pin "37") (pinfunction "P0.2_37") (pintype "unspecified"))
    )
    (net (code "7") (name "/P03") (class "Default")
      (node (ref "R10") (pin "1") (pinfunction "1_1") (pintype "unspecified"))
      (node (ref "RN1") (pin "5") (pinfunction "5_5") (pintype "input"))
      (node (ref "U1") (pin "36") (pinfunction "P0.3_36") (pintype "unspecified"))
    )
    (net (code "8") (name "/P04") (class "Default")
      (node (ref "R11") (pin "1") (pinfunction "1_1") (pintype "unspecified"))
      (node (ref "RN1") (pin "6") (pinfunction "6_6") (pintype "input"))
      (node (ref "U1") (pin "35") (pinfunction "P0.4_35") (pintype "unspecified"))
    )
    (net (code "9") (name "/P05") (class "Default")
      (node (ref "R12") (pin "1") (pinfunction "1_1") (pintype "unspecified"))
      (node (ref "RN1") (pin "7") (pinfunction "7_7") (pintype "input"))
      (node (ref "U1") (pin "34") (pinfunction "P0.5_34") (pintype "unspecified"))
    )
    (net (code "10") (name "/P06") (class "Default")
      (node (ref "R13") (pin "1") (pinfunction "1_1") (pintype "unspecified"))
      (node (ref "RN1") (pin "8") (pinfunction "8_8") (pintype "input"))
      (node (ref "U1") (pin "33") (pinfunction "P0.6_33") (pintype "unspecified"))
    )
    (net (code "11") (name "/P07") (class "Default")
      (node (ref "R14") (pin "1") (pinfunction "1_1") (pintype "unspecified"))
      (node (ref "RN1") (pin "9") (pinfunction "9_9") (pintype "input"))
      (node (ref "U1") (pin "32") (pinfunction "P0.7_32") (pintype "unspecified"))
    )
    (net (code "12") (name "/P10") (class "Default")
      (node (ref "R29") (pin "1") (pinfunction "1_1") (pintype "unspecified"))
      (node (ref "U1") (pin "1") (pinfunction "T2/P1.0_1") (pintype "unspecified"))
    )
    (net (code "13") (name "/P11") (class "Default")
      (node (ref "R30") (pin "1") (pinfunction "1_1") (pintype "unspecified"))
      (node (ref "U1") (pin "2") (pinfunction "T2EX/P1.1_2") (pintype "unspecified"))
    )
    (net (code "14") (name "/P12") (class "Default")
      (node (ref "R31") (pin "1") (pinfunction "1_1") (pintype "unspecified"))
      (node (ref "U1") (pin "3") (pinfunction "P1.2_3") (pintype "unspecified"))
    )
    (net (code "15") (name "/P13") (class "Default")
      (node (ref "R32") (pin "1") (pinfunction "1_1") (pintype "unspecified"))
      (node (ref "U1") (pin "4") (pinfunction "P1.3_4") (pintype "unspecified"))
    )
    (net (code "16") (name "/P14") (class "Default")
      (node (ref "R33") (pin "1") (pinfunction "1_1") (pintype "unspecified"))
      (node (ref "U1") (pin "5") (pinfunction "P1.4_5") (pintype "unspecified"))
    )
    (net (code "17") (name "/P15") (class "Default")
      (node (ref "R34") (pin "1") (pinfunction "1_1") (pintype "unspecified"))
      (node (ref "U1") (pin "6") (pinfunction "P1.5_6") (pintype "unspecified"))
    )
    (net (code "18") (name "/P16") (class "Default")
      (node (ref "R35") (pin "1") (pinfunction "1_1") (pintype "unspecified"))
      (node (ref "U1") (pin "7") (pinfunction "P1.6_7") (pintype "unspecified"))
    )
    (net (code "19") (name "/P17") (class "Default")
      (node (ref "R36") (pin "1") (pinfunction "1_1") (pintype "unspecified"))
      (node (ref "U1") (pin "8") (pinfunction "P1.7_8") (pintype "unspecified"))
    )
    (net (code "20") (name "/P20") (class "Default")
      (node (ref "R15") (pin "1") (pinfunction "1_1") (pintype "unspecified"))
      (node (ref "U1") (pin "21") (pinfunction "P2.0_21") (pintype "unspecified"))
    )
    (net (code "21") (name "/P21") (class "Default")
      (node (ref "R16") (pin "1") (pinfunction "1_1") (pintype "unspecified"))
      (node (ref "U1") (pin "22") (pinfunction "P2.1_22") (pintype "unspecified"))
    )
    (net (code "22") (name "/P22") (class "Default")
      (node (ref "R17") (pin "1") (pinfunction "1_1") (pintype "unspecified"))
      (node (ref "U1") (pin "23") (pinfunction "P2.2_23") (pintype "unspecified"))
    )
    (net (code "23") (name "/P23") (class "Default")
      (node (ref "R18") (pin "1") (pinfunction "1_1") (pintype "unspecified"))
      (node (ref "U1") (pin "24") (pinfunction "P2.3_24") (pintype "unspecified"))
    )
    (net (code "24") (name "/P24") (class "Default")
      (node (ref "R19") (pin "1") (pinfunction "1_1") (pintype "unspecified"))
      (node (ref "U1") (pin "25") (pinfunction "P2.4_25") (pintype "unspecified"))
    )
    (net (code "25") (name "/P25") (class "Default")
      (node (ref "R20") (pin "1") (pinfunction "1_1") (pintype "unspecified"))
      (node (ref "U1") (pin "26") (pinfunction "P2.5_26") (pintype "unspecified"))
    )
    (net (code "26") (name "/P26") (class "Default")
      (node (ref "R21") (pin "1") (pinfunction "1_1") (pintype "unspecified"))
      (node (ref "U1") (pin "27") (pinfunction "P2.6_27") (pintype "unspecified"))
    )
    (net (code "27") (name "/P27") (class "Default")
      (node (ref "R22") (pin "1") (pinfunction "1_1") (pintype "unspecified"))
      (node (ref "U1") (pin "28") (pinfunction "P2.7_28") (pintype "unspecified"))
    )
    (net (code "28") (name "/P32") (class "Default")
      (node (ref "R23") (pin "1") (pinfunction "1_1") (pintype "unspecified"))
      (node (ref "U1") (pin "12") (pinfunction "INT0#/P3.2_12") (pintype "unspecified"))
    )
    (net (code "29") (name "/P33") (class "Default")
      (node (ref "R24") (pin "1") (pinfunction "1_1") (pintype "unspecified"))
      (node (ref "U1") (pin "13") (pinfunction "INT1#/P3.3_13") (pintype "unspecified"))
    )
    (net (code "30") (name "/P34") (class "Default")
      (node (ref "R25") (pin "1") (pinfunction "1_1") (pintype "unspecified"))
      (node (ref "U1") (pin "14") (pinfunction "T0/P3.4_14") (pintype "unspecified"))
    )
    (net (code "31") (name "/P35") (class "Default")
      (node (ref "R26") (pin "1") (pinfunction "1_1") (pintype "unspecified"))
      (node (ref "U1") (pin "15") (pinfunction "T1/P3.5_15") (pintype "unspecified"))
    )
    (net (code "32") (name "/P36") (class "Default")
      (node (ref "R27") (pin "1") (pinfunction "1_1") (pintype "unspecified"))
      (node (ref "U1") (pin "16") (pinfunction "WR#/P3.6_16") (pintype "unspecified"))
    )
    (net (code "33") (name "/P37") (class "Default")
      (node (ref "R28") (pin "1") (pinfunction "1_1") (pintype "unspecified"))
      (node (ref "U1") (pin "17") (pinfunction "RD#/P3.7_17") (pintype "unspecified"))
    )
    (net (code "34") (name "/RST") (class "Default")
      (node (ref "C1") (pin "2") (pinfunction "2_2") (pintype "input"))
      (node (ref "R1") (pin "1") (pinfunction "1_1") (pintype "input"))
      (node (ref "SW1") (pin "3") (pinfunction "3_3") (pintype "unspecified"))
      (node (ref "SW1") (pin "4") (pinfunction "4_4") (pintype "unspecified"))
      (node (ref "U1") (pin "9") (pinfunction "RST_9") (pintype "unspecified"))
    )
    (net (code "35") (name "/RXD") (class "Default")
      (node (ref "U1") (pin "10") (pinfunction "RXD/P3.0_10") (pintype "unspecified"))
      (node (ref "U4") (pin "2") (pinfunction "TXD_2") (pintype "unspecified"))
    )
    (net (code "36") (name "/TXD") (class "Default")
      (node (ref "U1") (pin "11") (pinfunction "TXD/P3.1_11") (pintype "unspecified"))
      (node (ref "U4") (pin "3") (pinfunction "RXD_3") (pintype "unspecified"))
    )
    (net (code "37") (name "/XTAL1") (class "Default")
      (node (ref "U1") (pin "19") (pinfunction "XTAL1_19") (pintype "unspecified"))
      (node (ref "U2") (pin "2") (pinfunction "2_2") (pintype "unspecified"))
      (node (ref "X1") (pin "1") (pinfunction "OSC1_1") (pintype "input"))
    )
    (net (code "38") (name "/XTAL2") (class "Default")
      (node (ref "U1") (pin "18") (pinfunction "XTAL2_18") (pintype "unspecified"))
      (node (ref "U3") (pin "1") (pinfunction "1_1") (pintype "unspecified"))
      (node (ref "X1") (pin "2") (pinfunction "OSC2_2") (pintype "input"))
    )
    (net (code "39") (name "GND") (class "Default")
      (node (ref "C2") (pin "2") (pinfunction "2_2") (pintype "unspecified"))
      (node (ref "C4") (pin "2") (pinfunction "2_2") (pintype "unspecified"))
      (node (ref "C5") (pin "2") (pinfunction "2_2") (pintype "input"))
      (node (ref "C6") (pin "1") (pinfunction "1_1") (pintype "unspecified"))
      (node (ref "R1") (pin "2") (pinfunction "2_2") (pintype "input"))
      (node (ref "R5") (pin "2") (pinfunction "2_2") (pintype "unspecified"))
      (node (ref "R6") (pin "2") (pinfunction "2_2") (pintype "unspecified"))
      (node (ref "U1") (pin "20") (pinfunction "GND_20") (pintype "unspecified"))
      (node (ref "U2") (pin "1") (pinfunction "1_1") (pintype "unspecified"))
      (node (ref "U3") (pin "2") (pinfunction "2_2") (pintype "unspecified"))
      (node (ref "U4") (pin "1") (pinfunction "GND_1") (pintype "unspecified"))
      (node (ref "USB1") (pin "1") (pinfunction "GND_1") (pintype "unspecified"))
      (node (ref "USB1") (pin "12") (pinfunction "GND_12") (pintype "unspecified"))
      (node (ref "USB1") (pin "13") (pinfunction "SHELL_13") (pintype "unspecified"))
      (node (ref "USB1") (pin "14") (pinfunction "SHELL_14") (pintype "unspecified"))
    )
    (net (code "40") (name "Net-(LED1-Pad2)") (class "Default")
      (node (ref "LED1") (pin "2") (pinfunction "2_2") (pintype "unspecified"))
      (node (ref "R7") (pin "2") (pinfunction "2_2") (pintype "unspecified"))
    )
    (net (code "41") (name "Net-(LED2-Pad2)") (class "Default")
      (node (ref "LED2") (pin "2") (pinfunction "2_2") (pintype "unspecified"))
      (node (ref "R8") (pin "2") (pinfunction "2_2") (pintype "unspecified"))
    )
    (net (code "42") (name "Net-(LED3-Pad2)") (class "Default")
      (node (ref "LED3") (pin "2") (pinfunction "2_2") (pintype "unspecified"))
      (node (ref "R9") (pin "2") (pinfunction "2_2") (pintype "unspecified"))
    )
    (net (code "43") (name "Net-(LED4-Pad2)") (class "Default")
      (node (ref "LED4") (pin "2") (pinfunction "2_2") (pintype "unspecified"))
      (node (ref "R10") (pin "2") (pinfunction "2_2") (pintype "unspecified"))
    )
    (net (code "44") (name "Net-(LED5-Pad2)") (class "Default")
      (node (ref "LED5") (pin "2") (pinfunction "2_2") (pintype "unspecified"))
      (node (ref "R11") (pin "2") (pinfunction "2_2") (pintype "unspecified"))
    )
    (net (code "45") (name "Net-(LED6-Pad2)") (class "Default")
      (node (ref "LED6") (pin "2") (pinfunction "2_2") (pintype "unspecified"))
      (node (ref "R12") (pin "2") (pinfunction "2_2") (pintype "unspecified"))
    )
    (net (code "46") (name "Net-(LED7-Pad2)") (class "Default")
      (node (ref "LED7") (pin "2") (pinfunction "2_2") (pintype "unspecified"))
      (node (ref "R13") (pin "2") (pinfunction "2_2") (pintype "unspecified"))
    )
    (net (code "47") (name "Net-(LED8-Pad2)") (class "Default")
      (node (ref "LED8") (pin "2") (pinfunction "2_2") (pintype "unspecified"))
      (node (ref "R14") (pin "2") (pinfunction "2_2") (pintype "unspecified"))
    )
    (net (code "48") (name "Net-(LED9-Pad2)") (class "Default")
      (node (ref "LED9") (pin "2") (pinfunction "2_2") (pintype "unspecified"))
      (node (ref "R15") (pin "2") (pinfunction "2_2") (pintype "unspecified"))
    )
    (net (code "49") (name "Net-(LED10-Pad2)") (class "Default")
      (node (ref "LED10") (pin "2") (pinfunction "2_2") (pintype "unspecified"))
      (node (ref "R16") (pin "2") (pinfunction "2_2") (pintype "unspecified"))
    )
    (net (code "50") (name "Net-(LED11-Pad2)") (class "Default")
      (node (ref "LED11") (pin "2") (pinfunction "2_2") (pintype "unspecified"))
      (node (ref "R17") (pin "2") (pinfunction "2_2") (pintype "unspecified"))
    )
    (net (code "51") (name "Net-(LED12-Pad2)") (class "Default")
      (node (ref "LED12") (pin "2") (pinfunction "2_2") (pintype "unspecified"))
      (node (ref "R18") (pin "2") (pinfunction "2_2") (pintype "unspecified"))
    )
    (net (code "52") (name "Net-(LED13-Pad2)") (class "Default")
      (node (ref "LED13") (pin "2") (pinfunction "2_2") (pintype "unspecified"))
      (node (ref "R19") (pin "2") (pinfunction "2_2") (pintype "unspecified"))
    )
    (net (code "53") (name "Net-(LED14-Pad2)") (class "Default")
      (node (ref "LED14") (pin "2") (pinfunction "2_2") (pintype "unspecified"))
      (node (ref "R20") (pin "2") (pinfunction "2_2") (pintype "unspecified"))
    )
    (net (code "54") (name "Net-(LED15-Pad2)") (class "Default")
      (node (ref "LED15") (pin "2") (pinfunction "2_2") (pintype "unspecified"))
      (node (ref "R21") (pin "2") (pinfunction "2_2") (pintype "unspecified"))
    )
    (net (code "55") (name "Net-(LED16-Pad2)") (class "Default")
      (node (ref "LED16") (pin "2") (pinfunction "2_2") (pintype "unspecified"))
      (node (ref "R22") (pin "2") (pinfunction "2_2") (pintype "unspecified"))
    )
    (net (code "56") (name "Net-(LED17-Pad2)") (class "Default")
      (node (ref "LED17") (pin "2") (pinfunction "2_2") (pintype "unspecified"))
      (node (ref "R23") (pin "2") (pinfunction "2_2") (pintype "unspecified"))
    )
    (net (code "57") (name "Net-(LED18-Pad2)") (class "Default")
      (node (ref "LED18") (pin "2") (pinfunction "2_2") (pintype "unspecified"))
      (node (ref "R24") (pin "2") (pinfunction "2_2") (pintype "unspecified"))
    )
    (net (code "58") (name "Net-(LED19-Pad2)") (class "Default")
      (node (ref "LED19") (pin "2") (pinfunction "2_2") (pintype "unspecified"))
      (node (ref "R25") (pin "2") (pinfunction "2_2") (pintype "unspecified"))
    )
    (net (code "59") (name "Net-(LED20-Pad2)") (class "Default")
      (node (ref "LED20") (pin "2") (pinfunction "2_2") (pintype "unspecified"))
      (node (ref "R26") (pin "2") (pinfunction "2_2") (pintype "unspecified"))
    )
    (net (code "60") (name "Net-(LED21-Pad2)") (class "Default")
      (node (ref "LED21") (pin "2") (pinfunction "2_2") (pintype "unspecified"))
      (node (ref "R27") (pin "2") (pinfunction "2_2") (pintype "unspecified"))
    )
    (net (code "61") (name "Net-(LED22-Pad2)") (class "Default")
      (node (ref "LED22") (pin "2") (pinfunction "2_2") (pintype "unspecified"))
      (node (ref "R28") (pin "2") (pinfunction "2_2") (pintype "unspecified"))
    )
    (net (code "62") (name "Net-(LED23-Pad2)") (class "Default")
      (node (ref "LED23") (pin "2") (pinfunction "2_2") (pintype "unspecified"))
      (node (ref "R29") (pin "2") (pinfunction "2_2") (pintype "unspecified"))
    )
    (net (code "63") (name "Net-(LED24-Pad2)") (class "Default")
      (node (ref "LED24") (pin "2") (pinfunction "2_2") (pintype "unspecified"))
      (node (ref "R30") (pin "2") (pinfunction "2_2") (pintype "unspecified"))
    )
    (net (code "64") (name "Net-(LED25-Pad2)") (class "Default")
      (node (ref "LED25") (pin "2") (pinfunction "2_2") (pintype "unspecified"))
      (node (ref "R31") (pin "2") (pinfunction "2_2") (pintype "unspecified"))
    )
    (net (code "65") (name "Net-(LED26-Pad2)") (class "Default")
      (node (ref "LED26") (pin "2") (pinfunction "2_2") (pintype "unspecified"))
      (node (ref "R32") (pin "2") (pinfunction "2_2") (pintype "unspecified"))
    )
    (net (code "66") (name "Net-(LED27-Pad2)") (class "Default")
      (node (ref "LED27") (pin "2") (pinfunction "2_2") (pintype "unspecified"))
      (node (ref "R33") (pin "2") (pinfunction "2_2") (pintype "unspecified"))
    )
    (net (code "67") (name "Net-(LED28-Pad2)") (class "Default")
      (node (ref "LED28") (pin "2") (pinfunction "2_2") (pintype "unspecified"))
      (node (ref "R34") (pin "2") (pinfunction "2_2") (pintype "unspecified"))
    )
    (net (code "68") (name "Net-(LED29-Pad2)") (class "Default")
      (node (ref "LED29") (pin "2") (pinfunction "2_2") (pintype "unspecified"))
      (node (ref "R35") (pin "2") (pinfunction "2_2") (pintype "unspecified"))
    )
    (net (code "69") (name "Net-(LED30-Pad2)") (class "Default")
      (node (ref "LED30") (pin "2") (pinfunction "2_2") (pintype "unspecified"))
      (node (ref "R36") (pin "2") (pinfunction "2_2") (pintype "unspecified"))
    )
    (net (code "70") (name "Net-(U4-UD+)") (class "Default")
      (node (ref "R3") (pin "2") (pinfunction "2_2") (pintype "unspecified"))
      (node (ref "U4") (pin "5") (pinfunction "UD+_5") (pintype "unspecified"))
    )
    (net (code "71") (name "Net-(U4-UD-)") (class "Default")
      (node (ref "R4") (pin "2") (pinfunction "2_2") (pintype "unspecified"))
      (node (ref "U4") (pin "6") (pinfunction "UD-_6") (pintype "unspecified"))
    )
    (net (code "72") (name "Net-(U4-V3)") (class "Default")
      (node (ref "C4") (pin "1") (pinfunction "1_1") (pintype "unspecified"))
      (node (ref "U4") (pin "4") (pinfunction "V3_4") (pintype "unspecified"))
    )
    (net (code "73") (name "Net-(U4-VCC)") (class "Default")
      (node (ref "C3") (pin "1") (pinfunction "1_1") (pintype "unspecified"))
      (node (ref "C5") (pin "1") (pinfunction "1_1") (pintype "input"))
      (node (ref "C6") (pin "2") (pinfunction "2_2") (pintype "unspecified"))
      (node (ref "U4") (pin "16") (pinfunction "VCC_16") (pintype "unspecified"))
    )
    (net (code "74") (name "Net-(USB1-CC1)") (class "Default")
      (node (ref "R5") (pin "1") (pinfunction "1_1") (pintype "unspecified"))
      (node (ref "USB1") (pin "4") (pinfunction "CC1_4") (pintype "unspecified"))
    )
    (net (code "75") (name "Net-(USB1-CC2)") (class "Default")
      (node (ref "R6") (pin "1") (pinfunction "1_1") (pintype "unspecified"))
      (node (ref "USB1") (pin "10") (pinfunction "CC2_10") (pintype "unspecified"))
    )
    (net (code "76") (name "VCC") (class "Default")
      (node (ref "C1") (pin "1") (pinfunction "1_1") (pintype "input"))
      (node (ref "C2") (pin "1") (pinfunction "1_1") (pintype "unspecified"))
      (node (ref "LED1") (pin "1") (pinfunction "1_1") (pintype "unspecified"))
      (node (ref "LED10") (pin "1") (pinfunction "1_1") (pintype "unspecified"))
      (node (ref "LED11") (pin "1") (pinfunction "1_1") (pintype "unspecified"))
      (node (ref "LED12") (pin "1") (pinfunction "1_1") (pintype "unspecified"))
      (node (ref "LED13") (pin "1") (pinfunction "1_1") (pintype "unspecified"))
      (node (ref "LED14") (pin "1") (pinfunction "1_1") (pintype "unspecified"))
      (node (ref "LED15") (pin "1") (pinfunction "1_1") (pintype "unspecified"))
      (node (ref "LED16") (pin "1") (pinfunction "1_1") (pintype "unspecified"))
      (node (ref "LED17") (pin "1") (pinfunction "1_1") (pintype "unspecified"))
      (node (ref "LED18") (pin "1") (pinfunction "1_1") (pintype "unspecified"))
      (node (ref "LED19") (pin "1") (pinfunction "1_1") (pintype "unspecified"))
      (node (ref "LED2") (pin "1") (pinfunction "1_1") (pintype "unspecified"))
      (node (ref "LED20") (pin "1") (pinfunction "1_1") (pintype "unspecified"))
      (node (ref "LED21") (pin "1") (pinfunction "1_1") (pintype "unspecified"))
      (node (ref "LED22") (pin "1") (pinfunction "1_1") (pintype "unspecified"))
      (node (ref "LED23") (pin "1") (pinfunction "1_1") (pintype "unspecified"))
      (node (ref "LED24") (pin "1") (pinfunction "1_1") (pintype "unspecified"))
      (node (ref "LED25") (pin "1") (pinfunction "1_1") (pintype "unspecified"))
      (node (ref "LED26") (pin "1") (pinfunction "1_1") (pintype "unspecified"))
      (node (ref "LED27") (pin "1") (pinfunction "1_1") (pintype "unspecified"))
      (node (ref "LED28") (pin "1") (pinfunction "1_1") (pintype "unspecified"))
      (node (ref "LED29") (pin "1") (pinfunction "1_1") (pintype "unspecified"))
      (node (ref "LED3") (pin "1") (pinfunction "1_1") (pintype "unspecified"))
      (node (ref "LED30") (pin "1") (pinfunction "1_1") (pintype "unspecified"))
      (node (ref "LED4") (pin "1") (pinfunction "1_1") (pintype "unspecified"))
      (node (ref "LED5") (pin "1") (pinfunction "1_1") (pintype "unspecified"))
      (node (ref "LED6") (pin "1") (pinfunction "1_1") (pintype "unspecified"))
      (node (ref "LED7") (pin "1") (pinfunction "1_1") (pintype "unspecified"))
      (node (ref "LED8") (pin "1") (pinfunction "1_1") (pintype "unspecified"))
      (node (ref "LED9") (pin "1") (pinfunction "1_1") (pintype "unspecified"))
      (node (ref "RN1") (pin "1") (pinfunction "1_1") (pintype "input"))
      (node (ref "SW1") (pin "1") (pinfunction "1_1") (pintype "unspecified"))
      (node (ref "SW1") (pin "2") (pinfunction "2_2") (pintype "unspecified"))
      (node (ref "SW2") (pin "2") (pinfunction "2_2") (pintype "unspecified"))
      (node (ref "SW2") (pin "3") (pinfunction "3_3") (pintype "unspecified"))
      (node (ref "SW2") (pin "5") (pinfunction "5_5") (pintype "unspecified"))
      (node (ref "SW2") (pin "6") (pinfunction "6_6") (pintype "unspecified"))
      (node (ref "U1") (pin "31") (pinfunction "EA#_31") (pintype "unspecified"))
      (node (ref "U1") (pin "40") (pinfunction "VCC_40") (pintype "unspecified"))
    )
    (net (code "77") (name "unconnected-(C3-Pad2)") (class "Default")
      (node (ref "C3") (pin "2") (pinfunction "2_2") (pintype "unspecified"))
    )
    (net (code "78") (name "unconnected-(U1-ALE-Pad30)") (class "Default")
      (node (ref "U1") (pin "30") (pinfunction "ALE_30") (pintype "unspecified+no_connect"))
    )
    (net (code "79") (name "unconnected-(U1-PSEN#-Pad29)") (class "Default")
      (node (ref "U1") (pin "29") (pinfunction "PSEN#_29") (pintype "unspecified+no_connect"))
    )
    (net (code "80") (name "unconnected-(U4-CTS#-Pad9)") (class "Default")
      (node (ref "U4") (pin "9") (pinfunction "CTS#_9") (pintype "unspecified+no_connect"))
    )
    (net (code "81") (name "unconnected-(U4-DCD#-Pad12)") (class "Default")
      (node (ref "U4") (pin "12") (pinfunction "DCD#_12") (pintype "unspecified+no_connect"))
    )
    (net (code "82") (name "unconnected-(U4-DSR#-Pad10)") (class "Default")
      (node (ref "U4") (pin "10") (pinfunction "DSR#_10") (pintype "unspecified+no_connect"))
    )
    (net (code "83") (name "unconnected-(U4-DTR#-Pad13)") (class "Default")
      (node (ref "U4") (pin "13") (pinfunction "DTR#_13") (pintype "unspecified+no_connect"))
    )
    (net (code "84") (name "unconnected-(U4-R232-Pad15)") (class "Default")
      (node (ref "U4") (pin "15") (pinfunction "R232_15") (pintype "unspecified+no_connect"))
    )
    (net (code "85") (name "unconnected-(U4-RI#-Pad11)") (class "Default")
      (node (ref "U4") (pin "11") (pinfunction "RI#_11") (pintype "unspecified+no_connect"))
    )
    (net (code "86") (name "unconnected-(U4-RTS#-Pad14)") (class "Default")
      (node (ref "U4") (pin "14") (pinfunction "RTS#_14") (pintype "unspecified+no_connect"))
    )
    (net (code "87") (name "unconnected-(U4-XI-Pad7)") (class "Default")
      (node (ref "U4") (pin "7") (pinfunction "XI_7") (pintype "unspecified+no_connect"))
    )
    (net (code "88") (name "unconnected-(U4-XO-Pad8)") (class "Default")
      (node (ref "U4") (pin "8") (pinfunction "XO_8") (pintype "unspecified+no_connect"))
    )
    (net (code "89") (name "unconnected-(USB1-SBU1-Pad9)") (class "Default")
      (node (ref "USB1") (pin "9") (pinfunction "SBU1_9") (pintype "unspecified+no_connect"))
    )
    (net (code "90") (name "unconnected-(USB1-SBU2-Pad3)") (class "Default")
      (node (ref "USB1") (pin "3") (pinfunction "SBU2_3") (pintype "unspecified+no_connect"))
    )
  )
)
